# DATN_Schematic.net
KiCad netlist of a schematic drawn in Altium Designer
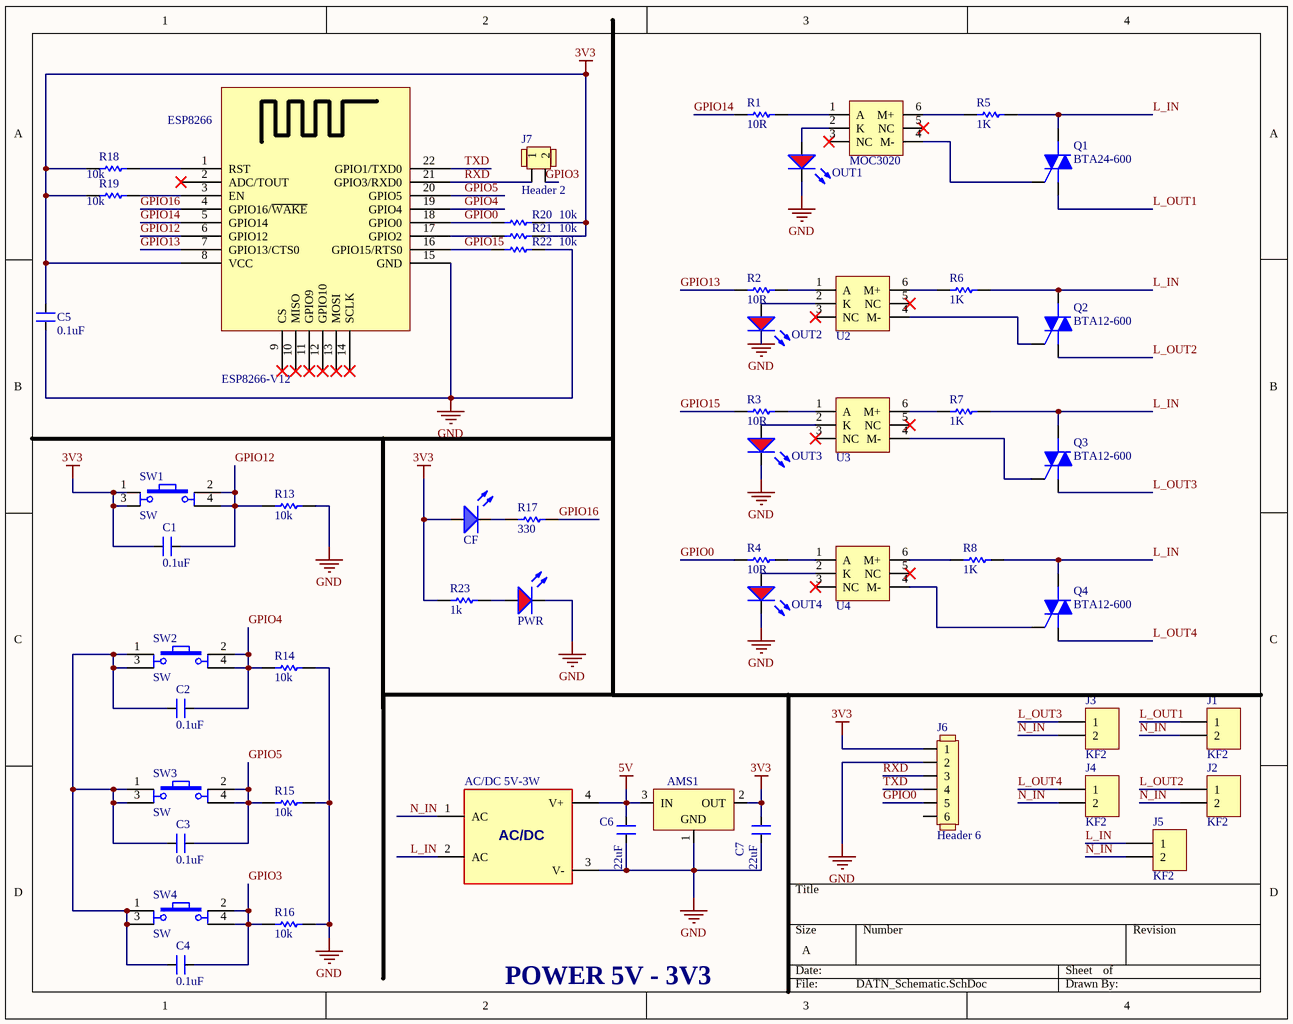
[diagram p0: DATN_Schematic.SchDoc]

(export (version "E")
  (design (tool "Eeschema 10.0.6"))
  (components
    (comp (ref "AC/DC 5V-3W")
      (value "5V3W-HLK-PM01")
      (footprint "HLK_PM01 5V3W")
      (libsource (lib "Duc") (part "5V3W-HLK-PM01"))
    )
    (comp (ref "AMS1")
      (value "AMS1117-3V3")
      (footprint "AMS1117")
      (description "Linear Voltage Regulator 3.3V 1A 15V Max SOT-223")
      (libsource (lib "Duc") (part "AMS1117-3V3"))
    )
    (comp (ref "C1")
      (value "0.1uF")
      (footprint "Cap 0805(2012)")
      (description "Ceramic Capacitor 1nF/50V (+-20% TH)/(+10%SMD)")
      (libsource (lib "Duc") (part "CAP_CER_0.1uF_50V_NPOL_1"))
    )
    (comp (ref "C2")
      (value "0.1uF")
      (footprint "Cap 0805(2012)")
      (description "Ceramic Capacitor 1nF/50V (+-20% TH)/(+10%SMD)")
      (libsource (lib "Duc") (part "CAP_CER_0.1uF_50V_NPOL_1"))
    )
    (comp (ref "C3")
      (value "0.1uF")
      (footprint "Cap 0805(2012)")
      (description "Ceramic Capacitor 1nF/50V (+-20% TH)/(+10%SMD)")
      (libsource (lib "Duc") (part "CAP_CER_0.1uF_50V_NPOL_1"))
    )
    (comp (ref "C4")
      (value "0.1uF")
      (footprint "Cap 0805(2012)")
      (description "Ceramic Capacitor 1nF/50V (+-20% TH)/(+10%SMD)")
      (libsource (lib "Duc") (part "CAP_CER_0.1uF_50V_NPOL_1"))
    )
    (comp (ref "C5")
      (value "0.1uF")
      (footprint "Cap 0805(2012)")
      (description "Ceramic Capacitor 1nF/50V (+-20% TH)/(+10%SMD)")
      (libsource (lib "Duc") (part "CAP_CER_0.1uF_50V_NPOL_1"))
    )
    (comp (ref "C6")
      (value "22uF")
      (footprint "Cap 0805(2012)")
      (description "Ceramic Capacitor 1nF/50V (+-20% TH)/(+10%SMD)")
      (libsource (lib "Duc") (part "CAP_CER_0.1uF_50V_NPOL_1"))
    )
    (comp (ref "C7")
      (value "22uF")
      (footprint "Cap 0805(2012)")
      (description "Ceramic Capacitor 1nF/50V (+-20% TH)/(+10%SMD)")
      (libsource (lib "Duc") (part "CAP_CER_0.1uF_50V_NPOL_1"))
    )
    (comp (ref "CF")
      (value "LED_BLUE")
      (footprint "LED0805BLUE")
      (description "LED Blue")
      (libsource (lib "Duc") (part "LED_BLUE"))
    )
    (comp (ref "ESP8266")
      (value "ESP8266-V12")
      (footprint "ESP-8266 V12")
      (libsource (lib "Duc") (part "ESP8266-V12"))
    )
    (comp (ref "J1")
      (value "KF2")
      (footprint "KF2-5.08")
      (fields
        (field (name "MANUFACTURER") "Würth Elektronik eiSos GmbH")
        (field (name "PARTNO") "691103110002")
        (field (name "CREATED BY") "Karrer Zheng")
      )
      (libsource (lib "LIBRARY_mualinhkien") (part "KF2"))
    )
    (comp (ref "J2")
      (value "KF2")
      (footprint "KF2-5.08")
      (fields
        (field (name "MANUFACTURER") "Würth Elektronik eiSos GmbH")
        (field (name "PARTNO") "691103110002")
        (field (name "CREATED BY") "Karrer Zheng")
      )
      (libsource (lib "LIBRARY_mualinhkien") (part "KF2"))
    )
    (comp (ref "J3")
      (value "KF2")
      (footprint "KF2-5.08")
      (fields
        (field (name "MANUFACTURER") "Würth Elektronik eiSos GmbH")
        (field (name "PARTNO") "691103110002")
        (field (name "CREATED BY") "Karrer Zheng")
      )
      (libsource (lib "LIBRARY_mualinhkien") (part "KF2"))
    )
    (comp (ref "J4")
      (value "KF2")
      (footprint "KF2-5.08")
      (fields
        (field (name "MANUFACTURER") "Würth Elektronik eiSos GmbH")
        (field (name "PARTNO") "691103110002")
        (field (name "CREATED BY") "Karrer Zheng")
      )
      (libsource (lib "LIBRARY_mualinhkien") (part "KF2"))
    )
    (comp (ref "J5")
      (value "KF2")
      (footprint "KF2-5.08")
      (fields
        (field (name "MANUFACTURER") "Würth Elektronik eiSos GmbH")
        (field (name "PARTNO") "691103110002")
        (field (name "CREATED BY") "Karrer Zheng")
      )
      (libsource (lib "LIBRARY_mualinhkien") (part "KF2"))
    )
    (comp (ref "J6") (value "Header 6") (footprint "HEADER x6") (libsource (lib "Duc") (part "Header 6")))
    (comp (ref "J7") (value "Header 2") (footprint "HEADER x2") (libsource (lib "Duc") (part "Header 2")))
    (comp (ref "MOC3020")
      (value "MOC3021M")
      (footprint "DIP6")
      (libsource (lib "LIBRARY_mualinhkien") (part "MOC3021M"))
    )
    (comp (ref "OUT1")
      (value "LED_RED")
      (footprint "LED0805RED")
      (description "LED Red")
      (libsource (lib "Duc") (part "LED_RED"))
    )
    (comp (ref "OUT2")
      (value "LED_RED")
      (footprint "LED0805RED")
      (description "LED Red")
      (libsource (lib "Duc") (part "LED_RED"))
    )
    (comp (ref "OUT3")
      (value "LED_RED")
      (footprint "LED0805RED")
      (description "LED Red")
      (libsource (lib "Duc") (part "LED_RED"))
    )
    (comp (ref "OUT4")
      (value "LED_RED")
      (footprint "LED0805RED")
      (description "LED Red")
      (libsource (lib "Duc") (part "LED_RED"))
    )
    (comp (ref "PWR")
      (value "LED_RED")
      (footprint "LED0805RED")
      (description "LED Red")
      (libsource (lib "Duc") (part "LED_RED"))
    )
    (comp (ref "Q1")
      (value "BTA24-600")
      (footprint "TO220H1")
      (description "Silicon Bidirectional Triode Thyristor")
      (fields (field (name "PUBLISHER") "Altium Limited"))
      (libsource (lib "LIBRARY_mualinhkien") (part "BTA12-600"))
    )
    (comp (ref "Q2")
      (value "BTA12-600")
      (footprint "TO220H1")
      (description "Silicon Bidirectional Triode Thyristor")
      (fields (field (name "PUBLISHER") "Altium Limited"))
      (libsource (lib "LIBRARY_mualinhkien") (part "BTA12-600"))
    )
    (comp (ref "Q3")
      (value "BTA12-600")
      (footprint "TO220H1")
      (description "Silicon Bidirectional Triode Thyristor")
      (fields (field (name "PUBLISHER") "Altium Limited"))
      (libsource (lib "LIBRARY_mualinhkien") (part "BTA12-600"))
    )
    (comp (ref "Q4")
      (value "BTA12-600")
      (footprint "TO220H1")
      (description "Silicon Bidirectional Triode Thyristor")
      (fields (field (name "PUBLISHER") "Altium Limited"))
      (libsource (lib "LIBRARY_mualinhkien") (part "BTA12-600"))
    )
    (comp (ref "R1")
      (value "10R")
      (footprint "Res 0805(2012)")
      (description "Resistor 0805")
      (libsource (lib "Duc") (part "Resistor 0805"))
    )
    (comp (ref "R2")
      (value "10R")
      (footprint "Res 0805(2012)")
      (description "Resistor 0805")
      (libsource (lib "Duc") (part "Resistor 0805"))
    )
    (comp (ref "R3")
      (value "10R")
      (footprint "Res 0805(2012)")
      (description "Resistor 0805")
      (libsource (lib "Duc") (part "Resistor 0805"))
    )
    (comp (ref "R4")
      (value "10R")
      (footprint "Res 0805(2012)")
      (description "Resistor 0805")
      (libsource (lib "Duc") (part "Resistor 0805"))
    )
    (comp (ref "R5")
      (value "1K")
      (footprint "Res 0805(2012)")
      (description "Resistor 0805")
      (libsource (lib "Duc") (part "Resistor 0805"))
    )
    (comp (ref "R6")
      (value "1K")
      (footprint "Res 0805(2012)")
      (description "Resistor 0805")
      (libsource (lib "Duc") (part "Resistor 0805"))
    )
    (comp (ref "R7")
      (value "1K")
      (footprint "Res 0805(2012)")
      (description "Resistor 0805")
      (libsource (lib "Duc") (part "Resistor 0805"))
    )
    (comp (ref "R8")
      (value "1K")
      (footprint "Res 0805(2012)")
      (description "Resistor 0805")
      (libsource (lib "Duc") (part "Resistor 0805"))
    )
    (comp (ref "R13")
      (value "10k")
      (footprint "Res 0805(2012)")
      (description "Resistor 0805")
      (libsource (lib "Duc") (part "Resistor 0805"))
    )
    (comp (ref "R14")
      (value "10k")
      (footprint "Res 0805(2012)")
      (description "Resistor 0805")
      (libsource (lib "Duc") (part "Resistor 0805"))
    )
    (comp (ref "R15")
      (value "10k")
      (footprint "Res 0805(2012)")
      (description "Resistor 0805")
      (libsource (lib "Duc") (part "Resistor 0805"))
    )
    (comp (ref "R16")
      (value "10k")
      (footprint "Res 0805(2012)")
      (description "Resistor 0805")
      (libsource (lib "Duc") (part "Resistor 0805"))
    )
    (comp (ref "R17")
      (value "330")
      (footprint "Res 0805(2012)")
      (description "Resistor 0805")
      (libsource (lib "Duc") (part "Resistor 0805"))
    )
    (comp (ref "R18")
      (value "10k")
      (footprint "Res 0805(2012)")
      (description "Resistor 0805")
      (libsource (lib "Duc") (part "Resistor 0805"))
    )
    (comp (ref "R19")
      (value "10k")
      (footprint "Res 0805(2012)")
      (description "Resistor 0805")
      (libsource (lib "Duc") (part "Resistor 0805"))
    )
    (comp (ref "R20")
      (value "10k")
      (footprint "Res 0805(2012)")
      (description "Resistor 0805")
      (libsource (lib "Duc") (part "Resistor 0805"))
    )
    (comp (ref "R21")
      (value "10k")
      (footprint "Res 0805(2012)")
      (description "Resistor 0805")
      (libsource (lib "Duc") (part "Resistor 0805"))
    )
    (comp (ref "R22")
      (value "10k")
      (footprint "Res 0805(2012)")
      (description "Resistor 0805")
      (libsource (lib "Duc") (part "Resistor 0805"))
    )
    (comp (ref "R23")
      (value "1k")
      (footprint "Res 0805(2012)")
      (description "Resistor 0805")
      (libsource (lib "Duc") (part "Resistor 0805"))
    )
    (comp (ref "SW1")
      (value "SW")
      (footprint "SWITCH 12X12")
      (description "Switch button 4 pin")
      (libsource (lib "syhaunguyen") (part "SW4"))
    )
    (comp (ref "SW2")
      (value "SW")
      (footprint "SWITCH 12X12")
      (description "Switch button 4 pin")
      (libsource (lib "syhaunguyen") (part "SW4"))
    )
    (comp (ref "SW3")
      (value "SW")
      (footprint "SWITCH 12X12")
      (description "Switch button 4 pin")
      (libsource (lib "syhaunguyen") (part "SW4"))
    )
    (comp (ref "SW4")
      (value "SW")
      (footprint "SWITCH 12X12")
      (description "Switch button 4 pin")
      (libsource (lib "syhaunguyen") (part "SW4"))
    )
    (comp (ref "U2")
      (value "MOC3021M")
      (footprint "DIP6")
      (libsource (lib "LIBRARY_mualinhkien") (part "MOC3021M"))
    )
    (comp (ref "U3")
      (value "MOC3021M")
      (footprint "DIP6")
      (libsource (lib "LIBRARY_mualinhkien") (part "MOC3021M"))
    )
    (comp (ref "U4")
      (value "MOC3021M")
      (footprint "DIP6")
      (libsource (lib "LIBRARY_mualinhkien") (part "MOC3021M"))
    )
  )
  (nets
    (net (code "1") (name "/GPIO0") (class "Default")
      (node (ref "ESP8266") (pin "18") (pinfunction "GPIO0_18") (pintype "passive"))
      (node (ref "J6") (pin "5") (pinfunction "5_5") (pintype "passive"))
      (node (ref "R20") (pin "2") (pinfunction "2_2") (pintype "passive"))
      (node (ref "R4") (pin "2") (pinfunction "2_2") (pintype "passive"))
    )
    (net (code "2") (name "/GPIO3") (class "Default")
      (node (ref "C4") (pin "2") (pinfunction "2_2") (pintype "passive"))
      (node (ref "J7") (pin "2") (pinfunction "2_2") (pintype "passive"))
      (node (ref "R16") (pin "2") (pinfunction "2_2") (pintype "passive"))
      (node (ref "SW4") (pin "2") (pintype "passive"))
      (node (ref "SW4") (pin "4") (pintype "passive"))
    )
    (net (code "3") (name "/GPIO4") (class "Default")
      (node (ref "C2") (pin "2") (pinfunction "2_2") (pintype "passive"))
      (node (ref "ESP8266") (pin "19") (pinfunction "GPIO4_19") (pintype "passive"))
      (node (ref "R14") (pin "2") (pinfunction "2_2") (pintype "passive"))
      (node (ref "SW2") (pin "2") (pintype "passive"))
      (node (ref "SW2") (pin "4") (pintype "passive"))
    )
    (net (code "4") (name "/GPIO5") (class "Default")
      (node (ref "C3") (pin "2") (pinfunction "2_2") (pintype "passive"))
      (node (ref "ESP8266") (pin "20") (pinfunction "GPIO5_20") (pintype "passive"))
      (node (ref "R15") (pin "2") (pinfunction "2_2") (pintype "passive"))
      (node (ref "SW3") (pin "2") (pintype "passive"))
      (node (ref "SW3") (pin "4") (pintype "passive"))
    )
    (net (code "5") (name "/GPIO12") (class "Default")
      (node (ref "C1") (pin "2") (pinfunction "2_2") (pintype "passive"))
      (node (ref "ESP8266") (pin "6") (pinfunction "GPIO12_6") (pintype "passive"))
      (node (ref "R13") (pin "2") (pinfunction "2_2") (pintype "passive"))
      (node (ref "SW1") (pin "2") (pintype "passive"))
      (node (ref "SW1") (pin "4") (pintype "passive"))
    )
    (net (code "6") (name "/GPIO13") (class "Default")
      (node (ref "ESP8266") (pin "7") (pinfunction "GPIO13/CTS0_7") (pintype "passive"))
      (node (ref "R2") (pin "2") (pinfunction "2_2") (pintype "passive"))
    )
    (net (code "7") (name "/GPIO14") (class "Default")
      (node (ref "ESP8266") (pin "5") (pinfunction "GPIO14_5") (pintype "passive"))
      (node (ref "R1") (pin "2") (pinfunction "2_2") (pintype "passive"))
    )
    (net (code "8") (name "/GPIO15") (class "Default")
      (node (ref "ESP8266") (pin "16") (pinfunction "GPIO15/RTS0_16") (pintype "passive"))
      (node (ref "R22") (pin "2") (pinfunction "2_2") (pintype "passive"))
      (node (ref "R3") (pin "2") (pinfunction "2_2") (pintype "passive"))
    )
    (net (code "9") (name "/GPIO16") (class "Default")
      (node (ref "ESP8266") (pin "4") (pinfunction "GPIO16/~{WAKE}_4") (pintype "passive"))
      (node (ref "R17") (pin "1") (pinfunction "1_1") (pintype "passive"))
    )
    (net (code "10") (name "/L_IN") (class "Default")
      (node (ref "AC/DC 5V-3W") (pin "2") (pinfunction "AC_2") (pintype "passive"))
      (node (ref "J5") (pin "1") (pinfunction "1_1") (pintype "passive"))
      (node (ref "Q1") (pin "2") (pinfunction "M2_2") (pintype "passive"))
      (node (ref "Q2") (pin "2") (pinfunction "M2_2") (pintype "passive"))
      (node (ref "Q3") (pin "2") (pinfunction "M2_2") (pintype "passive"))
      (node (ref "Q4") (pin "2") (pinfunction "M2_2") (pintype "passive"))
      (node (ref "R5") (pin "1") (pinfunction "1_1") (pintype "passive"))
      (node (ref "R6") (pin "1") (pinfunction "1_1") (pintype "passive"))
      (node (ref "R7") (pin "1") (pinfunction "1_1") (pintype "passive"))
      (node (ref "R8") (pin "1") (pinfunction "1_1") (pintype "passive"))
    )
    (net (code "11") (name "/L_OUT1") (class "Default")
      (node (ref "J1") (pin "1") (pinfunction "1_1") (pintype "passive"))
      (node (ref "Q1") (pin "1") (pinfunction "M1_1") (pintype "passive"))
    )
    (net (code "12") (name "/L_OUT2") (class "Default")
      (node (ref "J2") (pin "1") (pinfunction "1_1") (pintype "passive"))
      (node (ref "Q2") (pin "1") (pinfunction "M1_1") (pintype "passive"))
    )
    (net (code "13") (name "/L_OUT3") (class "Default")
      (node (ref "J3") (pin "1") (pinfunction "1_1") (pintype "passive"))
      (node (ref "Q3") (pin "1") (pinfunction "M1_1") (pintype "passive"))
    )
    (net (code "14") (name "/L_OUT4") (class "Default")
      (node (ref "J4") (pin "1") (pinfunction "1_1") (pintype "passive"))
      (node (ref "Q4") (pin "1") (pinfunction "M1_1") (pintype "passive"))
    )
    (net (code "15") (name "/N_IN") (class "Default")
      (node (ref "AC/DC 5V-3W") (pin "1") (pinfunction "AC_1") (pintype "passive"))
      (node (ref "J1") (pin "2") (pinfunction "2_2") (pintype "passive"))
      (node (ref "J2") (pin "2") (pinfunction "2_2") (pintype "passive"))
      (node (ref "J3") (pin "2") (pinfunction "2_2") (pintype "passive"))
      (node (ref "J4") (pin "2") (pinfunction "2_2") (pintype "passive"))
      (node (ref "J5") (pin "2") (pinfunction "2_2") (pintype "passive"))
    )
    (net (code "16") (name "/RXD") (class "Default")
      (node (ref "ESP8266") (pin "21") (pinfunction "GPIO3/RXD0_21") (pintype "passive"))
      (node (ref "J6") (pin "3") (pinfunction "3_3") (pintype "passive"))
      (node (ref "J7") (pin "1") (pinfunction "1_1") (pintype "passive"))
    )
    (net (code "17") (name "/TXD") (class "Default")
      (node (ref "ESP8266") (pin "22") (pinfunction "GPIO1/TXD0_22") (pintype "passive"))
      (node (ref "J6") (pin "4") (pinfunction "4_4") (pintype "passive"))
    )
    (net (code "18") (name "3V3") (class "Default")
      (node (ref "AMS1") (pin "2") (pinfunction "OUT_2") (pintype "power_in"))
      (node (ref "C1") (pin "1") (pinfunction "1_1") (pintype "passive"))
      (node (ref "C5") (pin "2") (pinfunction "2_2") (pintype "passive"))
      (node (ref "C7") (pin "2") (pinfunction "2_2") (pintype "passive"))
      (node (ref "CF") (pin "1") (pinfunction "A_1") (pintype "passive"))
      (node (ref "ESP8266") (pin "8") (pinfunction "VCC_8") (pintype "passive"))
      (node (ref "J6") (pin "1") (pinfunction "1_1") (pintype "passive"))
      (node (ref "R18") (pin "2") (pinfunction "2_2") (pintype "passive"))
      (node (ref "R19") (pin "2") (pinfunction "2_2") (pintype "passive"))
      (node (ref "R20") (pin "1") (pinfunction "1_1") (pintype "passive"))
      (node (ref "R21") (pin "1") (pinfunction "1_1") (pintype "passive"))
      (node (ref "R23") (pin "2") (pinfunction "2_2") (pintype "passive"))
      (node (ref "SW1") (pin "1") (pintype "passive"))
      (node (ref "SW1") (pin "3") (pintype "passive"))
    )
    (net (code "19") (name "5V") (class "Default")
      (node (ref "AC/DC 5V-3W") (pin "4") (pinfunction "V+_4") (pintype "passive"))
      (node (ref "AMS1") (pin "3") (pinfunction "IN_3") (pintype "power_in"))
      (node (ref "C6") (pin "2") (pinfunction "2_2") (pintype "passive"))
    )
    (net (code "20") (name "GND") (class "Default")
      (node (ref "AC/DC 5V-3W") (pin "3") (pinfunction "V-_3") (pintype "passive"))
      (node (ref "AMS1") (pin "1") (pinfunction "GND_1") (pintype "power_in"))
      (node (ref "C5") (pin "1") (pinfunction "1_1") (pintype "passive"))
      (node (ref "C6") (pin "1") (pinfunction "1_1") (pintype "passive"))
      (node (ref "C7") (pin "1") (pinfunction "1_1") (pintype "passive"))
      (node (ref "ESP8266") (pin "15") (pinfunction "GND_15") (pintype "passive"))
      (node (ref "J6") (pin "2") (pinfunction "2_2") (pintype "passive"))
      (node (ref "OUT1") (pin "2") (pinfunction "K_2") (pintype "passive"))
      (node (ref "OUT2") (pin "2") (pinfunction "K_2") (pintype "passive"))
      (node (ref "OUT3") (pin "2") (pinfunction "K_2") (pintype "passive"))
      (node (ref "OUT4") (pin "2") (pinfunction "K_2") (pintype "passive"))
      (node (ref "PWR") (pin "2") (pinfunction "K_2") (pintype "passive"))
      (node (ref "R13") (pin "1") (pinfunction "1_1") (pintype "passive"))
      (node (ref "R14") (pin "1") (pinfunction "1_1") (pintype "passive"))
      (node (ref "R15") (pin "1") (pinfunction "1_1") (pintype "passive"))
      (node (ref "R16") (pin "1") (pinfunction "1_1") (pintype "passive"))
      (node (ref "R22") (pin "1") (pinfunction "1_1") (pintype "passive"))
    )
    (net (code "21") (name "Net-(C2-Pad1)") (class "Default")
      (node (ref "C2") (pin "1") (pinfunction "1_1") (pintype "passive"))
      (node (ref "C3") (pin "1") (pinfunction "1_1") (pintype "passive"))
      (node (ref "C4") (pin "1") (pinfunction "1_1") (pintype "passive"))
      (node (ref "SW2") (pin "1") (pintype "passive"))
      (node (ref "SW2") (pin "3") (pintype "passive"))
      (node (ref "SW3") (pin "1") (pintype "passive"))
      (node (ref "SW3") (pin "3") (pintype "passive"))
      (node (ref "SW4") (pin "1") (pintype "passive"))
      (node (ref "SW4") (pin "3") (pintype "passive"))
    )
    (net (code "22") (name "Net-(CF-K)") (class "Default")
      (node (ref "CF") (pin "2") (pinfunction "K_2") (pintype "passive"))
      (node (ref "R17") (pin "2") (pinfunction "2_2") (pintype "passive"))
    )
    (net (code "23") (name "Net-(ESP8266-EN)") (class "Default")
      (node (ref "ESP8266") (pin "3") (pinfunction "EN_3") (pintype "passive"))
      (node (ref "R19") (pin "1") (pinfunction "1_1") (pintype "passive"))
    )
    (net (code "24") (name "Net-(ESP8266-GPIO2)") (class "Default")
      (node (ref "ESP8266") (pin "17") (pinfunction "GPIO2_17") (pintype "passive"))
      (node (ref "R21") (pin "2") (pinfunction "2_2") (pintype "passive"))
    )
    (net (code "25") (name "Net-(ESP8266-RST)") (class "Default")
      (node (ref "ESP8266") (pin "1") (pinfunction "RST_1") (pintype "passive"))
      (node (ref "R18") (pin "1") (pinfunction "1_1") (pintype "passive"))
    )
    (net (code "26") (name "Net-(MOC3020-A)") (class "Default")
      (node (ref "MOC3020") (pin "1") (pinfunction "A_1") (pintype "passive"))
      (node (ref "R1") (pin "1") (pinfunction "1_1") (pintype "passive"))
    )
    (net (code "27") (name "Net-(MOC3020-K)") (class "Default")
      (node (ref "MOC3020") (pin "2") (pinfunction "K_2") (pintype "passive"))
      (node (ref "OUT1") (pin "1") (pinfunction "A_1") (pintype "passive"))
    )
    (net (code "28") (name "Net-(MOC3020-M+)") (class "Default")
      (node (ref "MOC3020") (pin "6") (pinfunction "M+_6") (pintype "passive"))
      (node (ref "R5") (pin "2") (pinfunction "2_2") (pintype "passive"))
    )
    (net (code "29") (name "Net-(MOC3020-M-)") (class "Default")
      (node (ref "MOC3020") (pin "4") (pinfunction "M-_4") (pintype "passive"))
      (node (ref "Q1") (pin "3") (pinfunction "G_3") (pintype "passive"))
    )
    (net (code "30") (name "Net-(OUT2-A)") (class "Default")
      (node (ref "OUT2") (pin "1") (pinfunction "A_1") (pintype "passive"))
      (node (ref "U2") (pin "2") (pinfunction "K_2") (pintype "passive"))
    )
    (net (code "31") (name "Net-(OUT3-A)") (class "Default")
      (node (ref "OUT3") (pin "1") (pinfunction "A_1") (pintype "passive"))
      (node (ref "U3") (pin "2") (pinfunction "K_2") (pintype "passive"))
    )
    (net (code "32") (name "Net-(OUT4-A)") (class "Default")
      (node (ref "OUT4") (pin "1") (pinfunction "A_1") (pintype "passive"))
      (node (ref "U4") (pin "2") (pinfunction "K_2") (pintype "passive"))
    )
    (net (code "33") (name "Net-(PWR-A)") (class "Default")
      (node (ref "PWR") (pin "1") (pinfunction "A_1") (pintype "passive"))
      (node (ref "R23") (pin "1") (pinfunction "1_1") (pintype "passive"))
    )
    (net (code "34") (name "Net-(Q2-G)") (class "Default")
      (node (ref "Q2") (pin "3") (pinfunction "G_3") (pintype "passive"))
      (node (ref "U2") (pin "4") (pinfunction "M-_4") (pintype "passive"))
    )
    (net (code "35") (name "Net-(Q3-G)") (class "Default")
      (node (ref "Q3") (pin "3") (pinfunction "G_3") (pintype "passive"))
      (node (ref "U3") (pin "4") (pinfunction "M-_4") (pintype "passive"))
    )
    (net (code "36") (name "Net-(Q4-G)") (class "Default")
      (node (ref "Q4") (pin "3") (pinfunction "G_3") (pintype "passive"))
      (node (ref "U4") (pin "4") (pinfunction "M-_4") (pintype "passive"))
    )
    (net (code "37") (name "Net-(U2-A)") (class "Default")
      (node (ref "R2") (pin "1") (pinfunction "1_1") (pintype "passive"))
      (node (ref "U2") (pin "1") (pinfunction "A_1") (pintype "passive"))
    )
    (net (code "38") (name "Net-(U2-M+)") (class "Default")
      (node (ref "R6") (pin "2") (pinfunction "2_2") (pintype "passive"))
      (node (ref "U2") (pin "6") (pinfunction "M+_6") (pintype "passive"))
    )
    (net (code "39") (name "Net-(U3-A)") (class "Default")
      (node (ref "R3") (pin "1") (pinfunction "1_1") (pintype "passive"))
      (node (ref "U3") (pin "1") (pinfunction "A_1") (pintype "passive"))
    )
    (net (code "40") (name "Net-(U3-M+)") (class "Default")
      (node (ref "R7") (pin "2") (pinfunction "2_2") (pintype "passive"))
      (node (ref "U3") (pin "6") (pinfunction "M+_6") (pintype "passive"))
    )
    (net (code "41") (name "Net-(U4-A)") (class "Default")
      (node (ref "R4") (pin "1") (pinfunction "1_1") (pintype "passive"))
      (node (ref "U4") (pin "1") (pinfunction "A_1") (pintype "passive"))
    )
    (net (code "42") (name "Net-(U4-M+)") (class "Default")
      (node (ref "R8") (pin "2") (pinfunction "2_2") (pintype "passive"))
      (node (ref "U4") (pin "6") (pinfunction "M+_6") (pintype "passive"))
    )
    (net (code "43") (name "unconnected-(AMS1-OUT-Pad4)") (class "Default")
      (node (ref "AMS1") (pin "4") (pinfunction "OUT_4") (pintype "power_in"))
    )
    (net (code "44") (name "unconnected-(ESP8266-ADC{slash}TOUT-Pad2)") (class "Default")
      (node (ref "ESP8266") (pin "2") (pinfunction "ADC/TOUT_2") (pintype "passive+no_connect"))
    )
    (net (code "45") (name "unconnected-(ESP8266-CS-Pad9)") (class "Default")
      (node (ref "ESP8266") (pin "9") (pinfunction "CS_9") (pintype "passive+no_connect"))
    )
    (net (code "46") (name "unconnected-(ESP8266-GPIO9-Pad11)") (class "Default")
      (node (ref "ESP8266") (pin "11") (pinfunction "GPIO9_11") (pintype "passive+no_connect"))
    )
    (net (code "47") (name "unconnected-(ESP8266-GPIO10-Pad12)") (class "Default")
      (node (ref "ESP8266") (pin "12") (pinfunction "GPIO10_12") (pintype "passive+no_connect"))
    )
    (net (code "48") (name "unconnected-(ESP8266-MISO-Pad10)") (class "Default")
      (node (ref "ESP8266") (pin "10") (pinfunction "MISO_10") (pintype "passive+no_connect"))
    )
    (net (code "49") (name "unconnected-(ESP8266-MOSI-Pad13)") (class "Default")
      (node (ref "ESP8266") (pin "13") (pinfunction "MOSI_13") (pintype "passive+no_connect"))
    )
    (net (code "50") (name "unconnected-(ESP8266-SCLK-Pad14)") (class "Default")
      (node (ref "ESP8266") (pin "14") (pinfunction "SCLK_14") (pintype "passive+no_connect"))
    )
    (net (code "51") (name "unconnected-(J6-Pad6)") (class "Default")
      (node (ref "J6") (pin "6") (pinfunction "6_6") (pintype "passive"))
    )
    (net (code "52") (name "unconnected-(MOC3020-NC-Pad3)") (class "Default")
      (node (ref "MOC3020") (pin "3") (pinfunction "NC_3") (pintype "passive+no_connect"))
    )
    (net (code "53") (name "unconnected-(MOC3020-NC-Pad5)") (class "Default")
      (node (ref "MOC3020") (pin "5") (pinfunction "NC_5") (pintype "passive+no_connect"))
    )
    (net (code "54") (name "unconnected-(U2-NC-Pad3)") (class "Default")
      (node (ref "U2") (pin "3") (pinfunction "NC_3") (pintype "passive+no_connect"))
    )
    (net (code "55") (name "unconnected-(U2-NC-Pad5)") (class "Default")
      (node (ref "U2") (pin "5") (pinfunction "NC_5") (pintype "passive+no_connect"))
    )
    (net (code "56") (name "unconnected-(U3-NC-Pad3)") (class "Default")
      (node (ref "U3") (pin "3") (pinfunction "NC_3") (pintype "passive+no_connect"))
    )
    (net (code "57") (name "unconnected-(U3-NC-Pad5)") (class "Default")
      (node (ref "U3") (pin "5") (pinfunction "NC_5") (pintype "passive+no_connect"))
    )
    (net (code "58") (name "unconnected-(U4-NC-Pad3)") (class "Default")
      (node (ref "U4") (pin "3") (pinfunction "NC_3") (pintype "passive+no_connect"))
    )
    (net (code "59") (name "unconnected-(U4-NC-Pad5)") (class "Default")
      (node (ref "U4") (pin "5") (pinfunction "NC_5") (pintype "passive+no_connect"))
    )
  )
)
